# ardusb.net
KiCad netlist of a schematic drawn in EAGLE
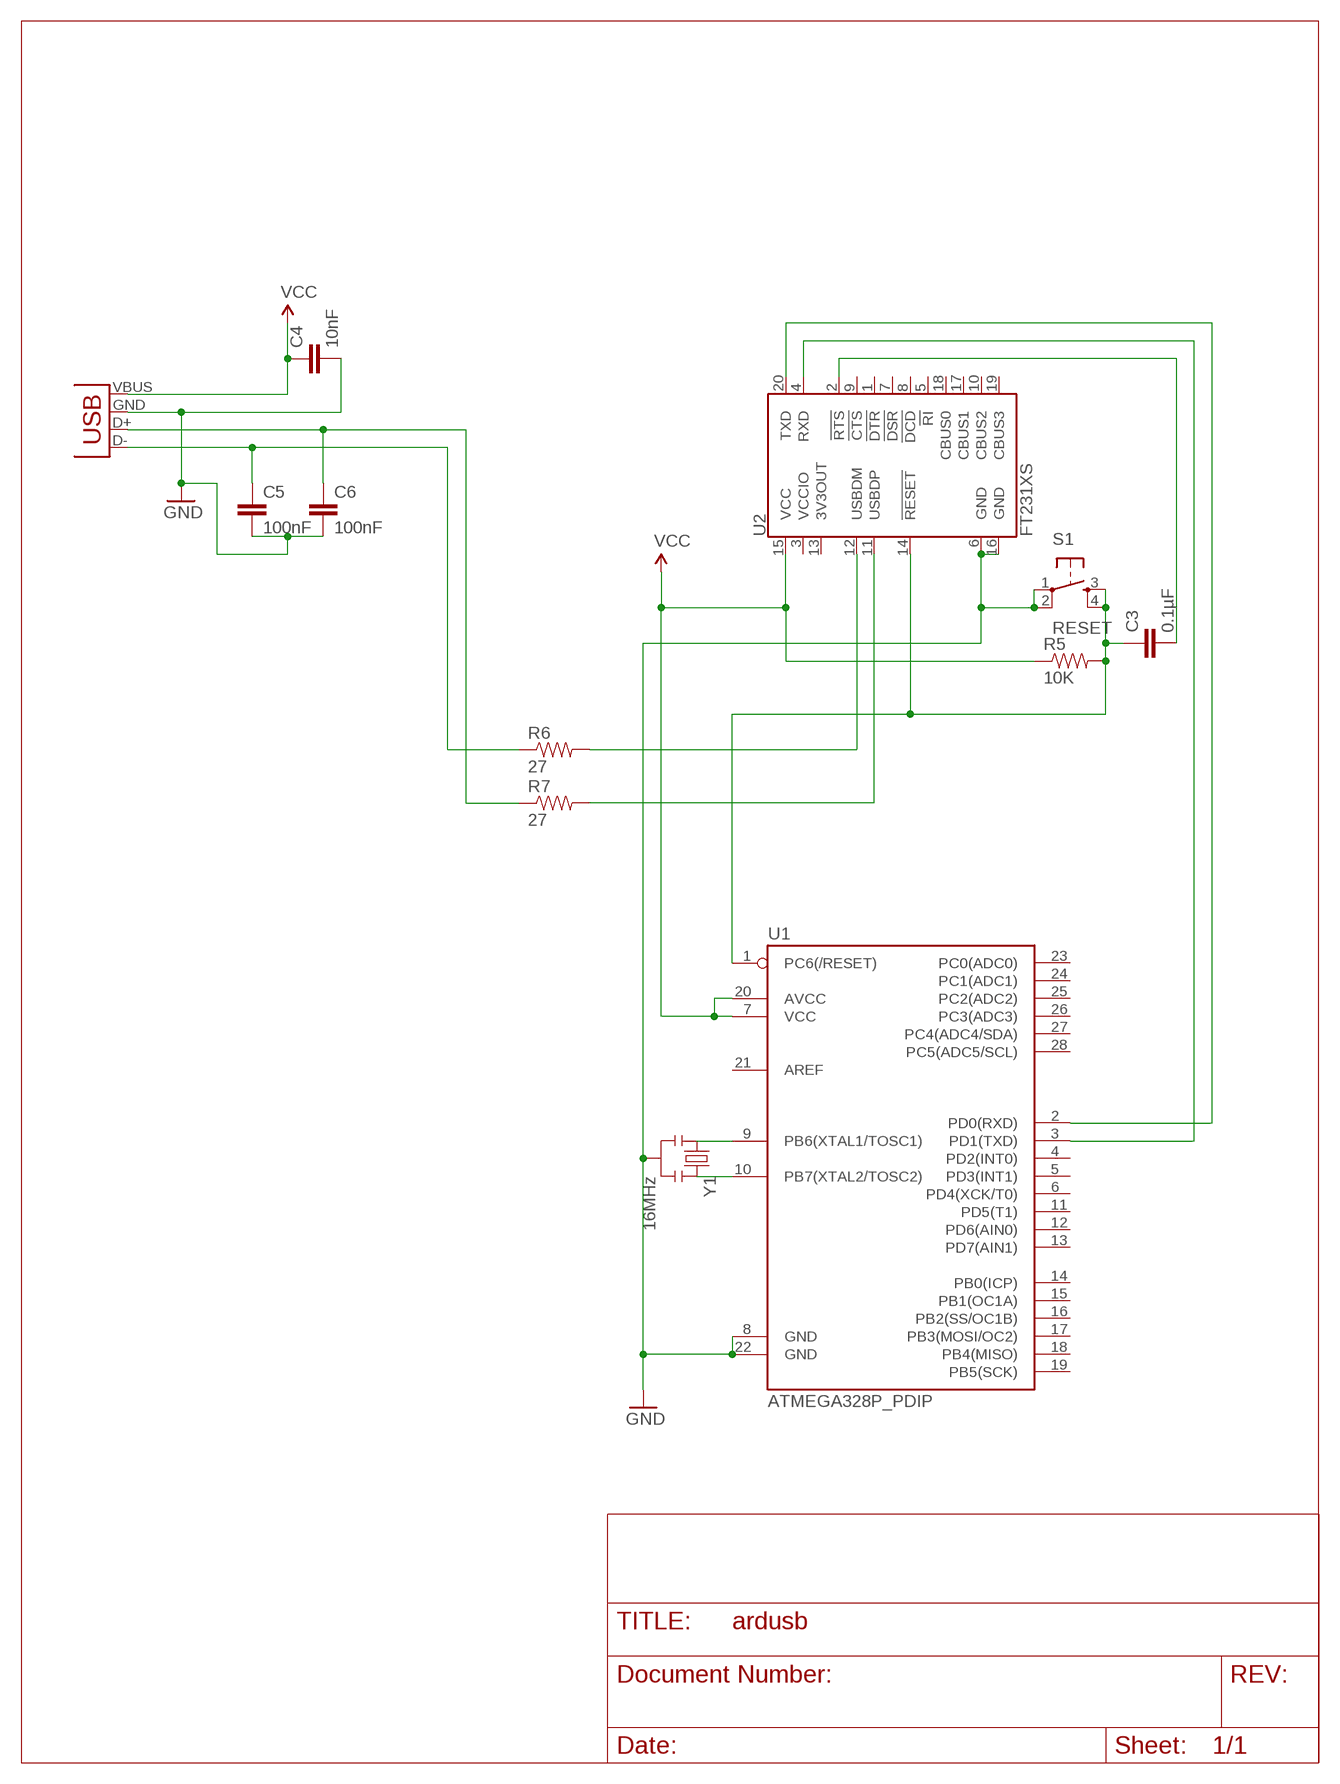
[diagram p0: schematic, sheet 1]

(export (version "E")
  (design (tool "Eeschema 10.0.6"))
  (components
    (comp (ref "C3")
      (value "0.1µF")
      (footprint "eagle-import:CAP-PTH-SMALL")
      (libsource (lib "eagle-import") (part "SparkFun-Passives_CAPPTH"))
    )
    (comp (ref "C4")
      (value "10nF")
      (footprint "eagle-import:CAP-PTH-SMALL")
      (libsource (lib "eagle-import") (part "SparkFun-Passives_CAPPTH"))
    )
    (comp (ref "C5")
      (value "100nF")
      (footprint "eagle-import:CAP-PTH-SMALL")
      (libsource (lib "eagle-import") (part "CAPPTH"))
    )
    (comp (ref "C6")
      (value "100nF")
      (footprint "eagle-import:CAP-PTH-SMALL")
      (libsource (lib "eagle-import") (part "CAPPTH"))
    )
    (comp (ref "JP1")
      (value "USB-A-H")
      (footprint "eagle-import:USB-A-H")
      (libsource (lib "eagle-import") (part "USB-A-H"))
    )
    (comp (ref "R5")
      (value "10K")
      (footprint "eagle-import:AXIAL-0.6")
      (libsource (lib "eagle-import") (part "RESISTORPTH-1W"))
    )
    (comp (ref "R6")
      (value "27")
      (footprint "eagle-import:AXIAL-0.6")
      (libsource (lib "eagle-import") (part "RESISTORPTH-1W"))
    )
    (comp (ref "R7")
      (value "27")
      (footprint "eagle-import:AXIAL-0.6")
      (libsource (lib "eagle-import") (part "RESISTORPTH-1W"))
    )
    (comp (ref "S1")
      (value "RESET")
      (footprint "eagle-import:TACTILE-PTH")
      (libsource (lib "eagle-import") (part "TAC_SWITCHPTH"))
    )
    (comp (ref "U1")
      (value "ATMEGA328P_PDIP")
      (footprint "eagle-import:DIL28-3")
      (libsource (lib "eagle-import") (part "ATMEGA328P_PDIP"))
    )
    (comp (ref "U2")
      (value "FT231XS")
      (footprint "eagle-import:SSOP20_L")
      (libsource (lib "eagle-import") (part "FT231XS"))
    )
    (comp (ref "Y1")
      (value "16MHz")
      (footprint "eagle-import:RESONATOR-PTH")
      (libsource (lib "eagle-import") (part "RESONATORPTH"))
    )
  )
  (nets
    (net (code "1") (name "GND") (class "Default")
      (node (ref "C4") (pin "2") (pinfunction "2_2") (pintype "passive"))
      (node (ref "C5") (pin "2") (pinfunction "2_2") (pintype "passive"))
      (node (ref "C6") (pin "2") (pinfunction "2_2") (pintype "passive"))
      (node (ref "JP1") (pin "GND") (pinfunction "VBUS_GND") (pintype "bidirectional"))
      (node (ref "S1") (pin "1") (pinfunction "1_1") (pintype "passive"))
      (node (ref "S1") (pin "2") (pinfunction "2_2") (pintype "passive"))
      (node (ref "U1") (pin "22") (pinfunction "GND_22") (pintype "bidirectional"))
      (node (ref "U1") (pin "8") (pinfunction "GND_8") (pintype "bidirectional"))
      (node (ref "U2") (pin "16") (pinfunction "GND_16") (pintype "bidirectional"))
      (node (ref "U2") (pin "6") (pinfunction "GND_6") (pintype "bidirectional"))
      (node (ref "Y1") (pin "2") (pinfunction "2_2") (pintype "passive"))
    )
    (net (code "2") (name "Net-(JP1-D+)") (class "Default")
      (node (ref "C5") (pin "1") (pinfunction "1_1") (pintype "passive"))
      (node (ref "JP1") (pin "D-") (pinfunction "D+_D-") (pintype "bidirectional"))
      (node (ref "R6") (pin "P$1") (pinfunction "1_P$1") (pintype "passive"))
    )
    (net (code "3") (name "Net-(JP1-D-)") (class "Default")
      (node (ref "C6") (pin "1") (pinfunction "1_1") (pintype "passive"))
      (node (ref "JP1") (pin "D+") (pinfunction "D-_D+") (pintype "bidirectional"))
      (node (ref "R7") (pin "P$1") (pinfunction "1_P$1") (pintype "passive"))
    )
    (net (code "4") (name "Net-(R5-2)") (class "Default")
      (node (ref "C3") (pin "1") (pinfunction "1_1") (pintype "passive"))
      (node (ref "R5") (pin "P$2") (pinfunction "2_P$2") (pintype "passive"))
      (node (ref "S1") (pin "3") (pinfunction "3_3") (pintype "passive"))
      (node (ref "S1") (pin "4") (pinfunction "4_4") (pintype "passive"))
      (node (ref "U1") (pin "1") (pinfunction "PC6(/RESET)_1") (pintype "bidirectional"))
      (node (ref "U2") (pin "14") (pinfunction "~{RESET}_14") (pintype "bidirectional"))
    )
    (net (code "5") (name "Net-(R6-2)") (class "Default")
      (node (ref "R6") (pin "P$2") (pinfunction "2_P$2") (pintype "passive"))
      (node (ref "U2") (pin "12") (pinfunction "USBDM_12") (pintype "bidirectional"))
    )
    (net (code "6") (name "Net-(R7-2)") (class "Default")
      (node (ref "R7") (pin "P$2") (pinfunction "2_P$2") (pintype "passive"))
      (node (ref "U2") (pin "11") (pinfunction "USBDP_11") (pintype "bidirectional"))
    )
    (net (code "7") (name "Net-(U1-PB6(XTAL1{slash}TOSC1))") (class "Default")
      (node (ref "U1") (pin "9") (pinfunction "PB6(XTAL1/TOSC1)_9") (pintype "bidirectional"))
      (node (ref "Y1") (pin "1") (pinfunction "1_1") (pintype "passive"))
    )
    (net (code "8") (name "Net-(U1-PB7(XTAL2{slash}TOSC2))") (class "Default")
      (node (ref "U1") (pin "10") (pinfunction "PB7(XTAL2/TOSC2)_10") (pintype "bidirectional"))
      (node (ref "Y1") (pin "3") (pinfunction "3_3") (pintype "passive"))
    )
    (net (code "9") (name "Net-(U1-PD0(RXD))") (class "Default")
      (node (ref "U1") (pin "2") (pinfunction "PD0(RXD)_2") (pintype "bidirectional"))
      (node (ref "U2") (pin "20") (pinfunction "TXD_20") (pintype "bidirectional"))
    )
    (net (code "10") (name "Net-(U1-PD1(TXD))") (class "Default")
      (node (ref "U1") (pin "3") (pinfunction "PD1(TXD)_3") (pintype "bidirectional"))
      (node (ref "U2") (pin "4") (pinfunction "RXD_4") (pintype "bidirectional"))
    )
    (net (code "11") (name "Net-(U2-~{RTS})") (class "Default")
      (node (ref "C3") (pin "2") (pinfunction "2_2") (pintype "passive"))
      (node (ref "U2") (pin "2") (pinfunction "~{RTS}_2") (pintype "bidirectional"))
    )
    (net (code "12") (name "VCC") (class "Default")
      (node (ref "C4") (pin "1") (pinfunction "1_1") (pintype "passive"))
      (node (ref "JP1") (pin "VBUS") (pinfunction "GND_VBUS") (pintype "bidirectional"))
      (node (ref "R5") (pin "P$1") (pinfunction "1_P$1") (pintype "passive"))
      (node (ref "U1") (pin "20") (pinfunction "AVCC_20") (pintype "bidirectional"))
      (node (ref "U1") (pin "7") (pinfunction "VCC_7") (pintype "bidirectional"))
      (node (ref "U2") (pin "15") (pinfunction "VCC_15") (pintype "bidirectional"))
    )
    (net (code "13") (name "unconnected-(U1-AREF-Pad21)") (class "Default")
      (node (ref "U1") (pin "21") (pinfunction "AREF_21") (pintype "bidirectional"))
    )
    (net (code "14") (name "unconnected-(U1-PB0(ICP)-Pad14)") (class "Default")
      (node (ref "U1") (pin "14") (pinfunction "PB0(ICP)_14") (pintype "bidirectional"))
    )
    (net (code "15") (name "unconnected-(U1-PB1(OC1A)-Pad15)") (class "Default")
      (node (ref "U1") (pin "15") (pinfunction "PB1(OC1A)_15") (pintype "bidirectional"))
    )
    (net (code "16") (name "unconnected-(U1-PB2(SS{slash}OC1B)-Pad16)") (class "Default")
      (node (ref "U1") (pin "16") (pinfunction "PB2(SS/OC1B)_16") (pintype "bidirectional"))
    )
    (net (code "17") (name "unconnected-(U1-PB3(MOSI{slash}OC2)-Pad17)") (class "Default")
      (node (ref "U1") (pin "17") (pinfunction "PB3(MOSI/OC2)_17") (pintype "bidirectional"))
    )
    (net (code "18") (name "unconnected-(U1-PB4(MISO)-Pad18)") (class "Default")
      (node (ref "U1") (pin "18") (pinfunction "PB4(MISO)_18") (pintype "bidirectional"))
    )
    (net (code "19") (name "unconnected-(U1-PB5(SCK)-Pad19)") (class "Default")
      (node (ref "U1") (pin "19") (pinfunction "PB5(SCK)_19") (pintype "bidirectional"))
    )
    (net (code "20") (name "unconnected-(U1-PC0(ADC0)-Pad23)") (class "Default")
      (node (ref "U1") (pin "23") (pinfunction "PC0(ADC0)_23") (pintype "bidirectional"))
    )
    (net (code "21") (name "unconnected-(U1-PC1(ADC1)-Pad24)") (class "Default")
      (node (ref "U1") (pin "24") (pinfunction "PC1(ADC1)_24") (pintype "bidirectional"))
    )
    (net (code "22") (name "unconnected-(U1-PC2(ADC2)-Pad25)") (class "Default")
      (node (ref "U1") (pin "25") (pinfunction "PC2(ADC2)_25") (pintype "bidirectional"))
    )
    (net (code "23") (name "unconnected-(U1-PC3(ADC3)-Pad26)") (class "Default")
      (node (ref "U1") (pin "26") (pinfunction "PC3(ADC3)_26") (pintype "bidirectional"))
    )
    (net (code "24") (name "unconnected-(U1-PC4(ADC4{slash}SDA)-Pad27)") (class "Default")
      (node (ref "U1") (pin "27") (pinfunction "PC4(ADC4/SDA)_27") (pintype "bidirectional"))
    )
    (net (code "25") (name "unconnected-(U1-PC5(ADC5{slash}SCL)-Pad28)") (class "Default")
      (node (ref "U1") (pin "28") (pinfunction "PC5(ADC5/SCL)_28") (pintype "bidirectional"))
    )
    (net (code "26") (name "unconnected-(U1-PD2(INT0)-Pad4)") (class "Default")
      (node (ref "U1") (pin "4") (pinfunction "PD2(INT0)_4") (pintype "bidirectional"))
    )
    (net (code "27") (name "unconnected-(U1-PD3(INT1)-Pad5)") (class "Default")
      (node (ref "U1") (pin "5") (pinfunction "PD3(INT1)_5") (pintype "bidirectional"))
    )
    (net (code "28") (name "unconnected-(U1-PD4(XCK{slash}T0)-Pad6)") (class "Default")
      (node (ref "U1") (pin "6") (pinfunction "PD4(XCK/T0)_6") (pintype "bidirectional"))
    )
    (net (code "29") (name "unconnected-(U1-PD5(T1)-Pad11)") (class "Default")
      (node (ref "U1") (pin "11") (pinfunction "PD5(T1)_11") (pintype "bidirectional"))
    )
    (net (code "30") (name "unconnected-(U1-PD6(AIN0)-Pad12)") (class "Default")
      (node (ref "U1") (pin "12") (pinfunction "PD6(AIN0)_12") (pintype "bidirectional"))
    )
    (net (code "31") (name "unconnected-(U1-PD7(AIN1)-Pad13)") (class "Default")
      (node (ref "U1") (pin "13") (pinfunction "PD7(AIN1)_13") (pintype "bidirectional"))
    )
    (net (code "32") (name "unconnected-(U2-3V3OUT-Pad13)") (class "Default")
      (node (ref "U2") (pin "13") (pinfunction "3V3OUT_13") (pintype "bidirectional"))
    )
    (net (code "33") (name "unconnected-(U2-CBUS0-Pad18)") (class "Default")
      (node (ref "U2") (pin "18") (pinfunction "CBUS0_18") (pintype "bidirectional"))
    )
    (net (code "34") (name "unconnected-(U2-CBUS1-Pad17)") (class "Default")
      (node (ref "U2") (pin "17") (pinfunction "CBUS1_17") (pintype "bidirectional"))
    )
    (net (code "35") (name "unconnected-(U2-CBUS2-Pad10)") (class "Default")
      (node (ref "U2") (pin "10") (pinfunction "CBUS2_10") (pintype "bidirectional"))
    )
    (net (code "36") (name "unconnected-(U2-CBUS3-Pad19)") (class "Default")
      (node (ref "U2") (pin "19") (pinfunction "CBUS3_19") (pintype "bidirectional"))
    )
    (net (code "37") (name "unconnected-(U2-VCCIO-Pad3)") (class "Default")
      (node (ref "U2") (pin "3") (pinfunction "VCCIO_3") (pintype "bidirectional"))
    )
    (net (code "38") (name "unconnected-(U2-~{CTS}-Pad9)") (class "Default")
      (node (ref "U2") (pin "9") (pinfunction "~{CTS}_9") (pintype "bidirectional"))
    )
    (net (code "39") (name "unconnected-(U2-~{DCD}-Pad8)") (class "Default")
      (node (ref "U2") (pin "8") (pinfunction "~{DCD}_8") (pintype "bidirectional"))
    )
    (net (code "40") (name "unconnected-(U2-~{DSR}-Pad7)") (class "Default")
      (node (ref "U2") (pin "7") (pinfunction "~{DSR}_7") (pintype "bidirectional"))
    )
    (net (code "41") (name "unconnected-(U2-~{DTR}-Pad1)") (class "Default")
      (node (ref "U2") (pin "1") (pinfunction "~{DTR}_1") (pintype "bidirectional"))
    )
    (net (code "42") (name "unconnected-(U2-~{RI}-Pad5)") (class "Default")
      (node (ref "U2") (pin "5") (pinfunction "~{RI}_5") (pintype "bidirectional"))
    )
  )
)
